# TL494_17.net
KiCad netlist of a schematic drawn in Altium Designer
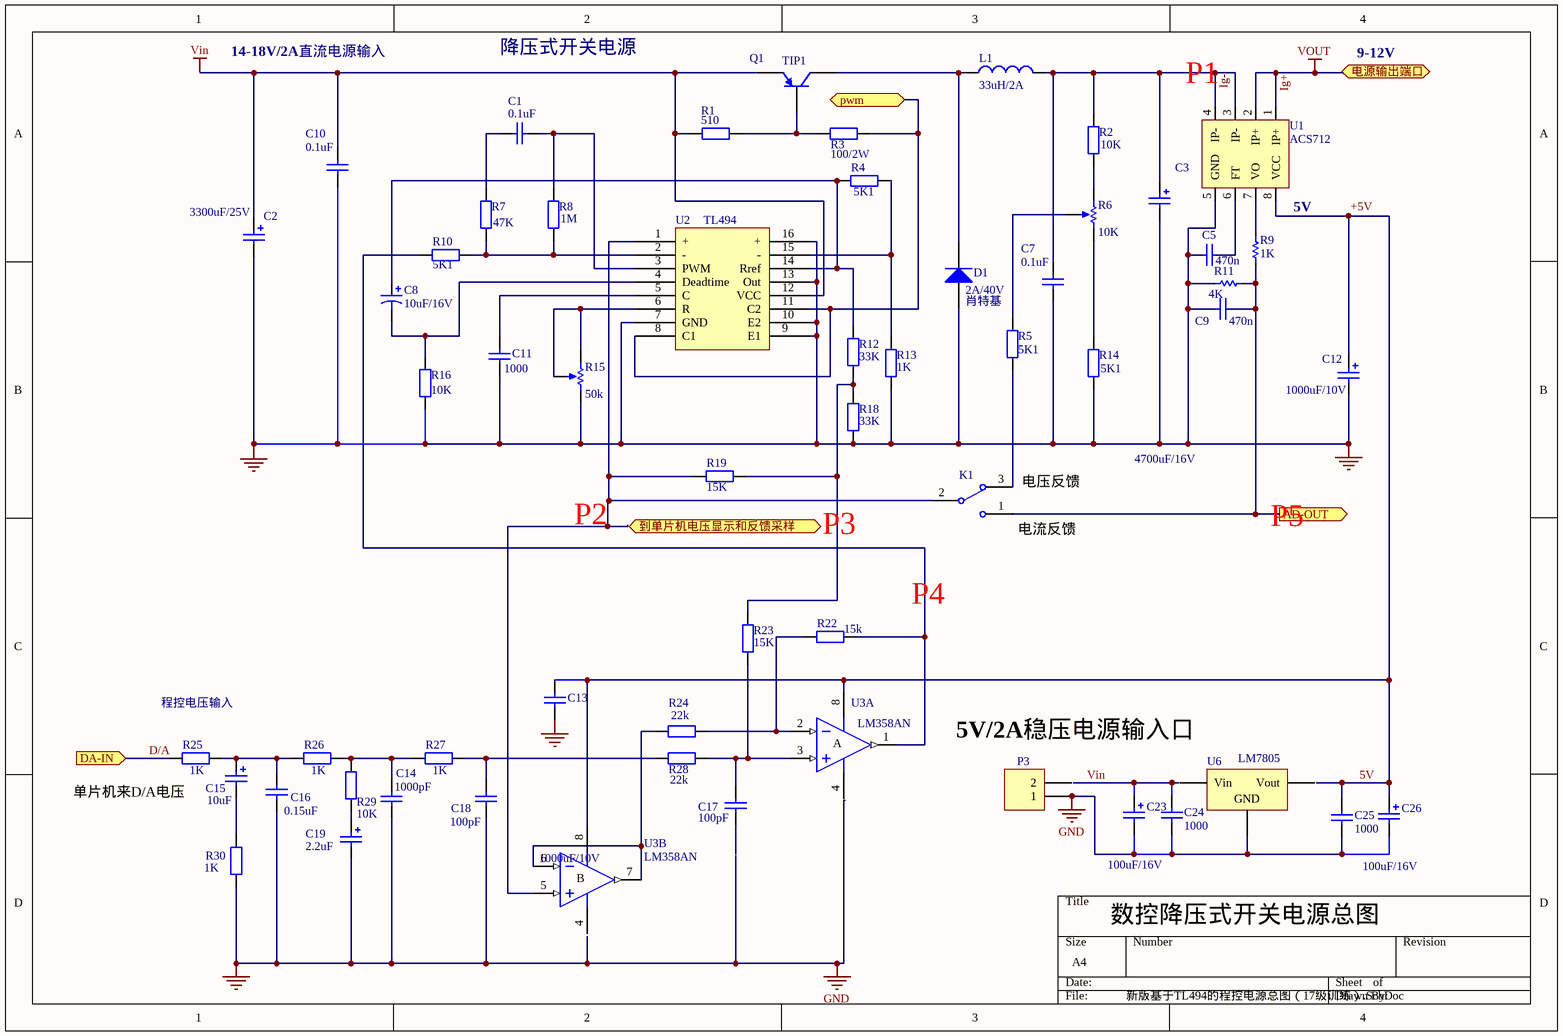
[diagram p0: 新版基于TL494的程控电源总图（17级训练）.SchDoc]

(export (version "E")
  (design (tool "Eeschema 10.0.6"))
  (components
    (comp (ref "C1")
      (value "0.1uF")
      (footprint "Cap")
      (description "Capacitor")
      (fields (field (name "Comment") "Cap") (field (name "PUBLISHER") "Altium Limited"))
      (libsource (lib "Miscellaneous Devices") (part "Cap"))
    )
    (comp (ref "C2")
      (value "3300uF/25V")
      (footprint "POLAR0.8")
      (description "Polarized Capacitor (Axial)")
      (fields (field (name "Comment") "Cap Pol2") (field (name "PUBLISHER") "Altium Limited"))
      (libsource (lib "Miscellaneous Devices") (part "Cap Pol2"))
    )
    (comp (ref "C3")
      (value "4700uF/16V")
      (footprint "POLAR0.8")
      (description "Polarized Capacitor (Axial)")
      (fields (field (name "Comment") "Cap Pol2") (field (name "PUBLISHER") "Altium Limited"))
      (libsource (lib "Miscellaneous Devices") (part "Cap Pol2"))
    )
    (comp (ref "C5")
      (value "470n")
      (footprint "1206")
      (description "ECQ-U2A334ML")
      (fields (field (name "Comment") "275VAC") (field (name "PUBLISHER") "Altium Limited"))
      (libsource (lib "Sheet1") (part "Cap"))
    )
    (comp (ref "C7")
      (value "0.1uF")
      (footprint "RAD-0.3")
      (description "Capacitor")
      (fields (field (name "Comment") "Cap") (field (name "PUBLISHER") "Altium Limited"))
      (libsource (lib "Miscellaneous Devices") (part "Cap"))
    )
    (comp (ref "C8")
      (value "10uF/16V")
      (footprint "RB7.6-15")
      (description "Polarized Capacitor (Radial)")
      (fields (field (name "Comment") "Cap Pol1") (field (name "PUBLISHER") "Altium Limited"))
      (libsource (lib "Miscellaneous Devices") (part "Cap Pol1"))
    )
    (comp (ref "C9")
      (value "470n")
      (footprint "1206")
      (description "ECQ-U2A334ML")
      (fields (field (name "Comment") "275VAC") (field (name "PUBLISHER") "Altium Limited"))
      (libsource (lib "Sheet1") (part "Cap"))
    )
    (comp (ref "C10")
      (value "0.1uF")
      (footprint "RAD-0.3")
      (description "Capacitor")
      (fields (field (name "Comment") "Cap") (field (name "PUBLISHER") "Altium Limited"))
      (libsource (lib "Miscellaneous Devices") (part "Cap"))
    )
    (comp (ref "C11")
      (value "1000")
      (footprint "Cap")
      (description "Capacitor")
      (fields (field (name "Comment") "Cap") (field (name "PUBLISHER") "Altium Limited"))
      (libsource (lib "Miscellaneous Devices") (part "Cap"))
    )
    (comp (ref "C12")
      (value "1000uF/10V")
      (footprint "POLAR0.8")
      (description "Polarized Capacitor (Axial)")
      (fields (field (name "Comment") "Cap Pol2") (field (name "PUBLISHER") "Altium Limited"))
      (libsource (lib "Miscellaneous Devices") (part "Cap Pol2"))
    )
    (comp (ref "C13")
      (value "1000uF/10V")
      (footprint "RAD-0.3")
      (description "Capacitor")
      (fields (field (name "Comment") "Cap") (field (name "PUBLISHER") "Altium Limited"))
      (libsource (lib "Miscellaneous Devices") (part "Cap"))
    )
    (comp (ref "C14")
      (value "1000pF")
      (footprint "RAD-0.3")
      (description "Capacitor")
      (fields (field (name "Comment") "Cap") (field (name "PUBLISHER") "Altium Limited"))
      (libsource (lib "Miscellaneous Devices") (part "Cap"))
    )
    (comp (ref "C15")
      (value "10uF")
      (footprint "RAD-0.3")
      (description "Polarized Capacitor (Axial)")
      (fields (field (name "Comment") "Cap Pol2") (field (name "PUBLISHER") "Altium Limited"))
      (libsource (lib "Miscellaneous Devices") (part "Cap Pol2"))
    )
    (comp (ref "C16")
      (value "0.15uF")
      (footprint "RAD-0.3")
      (description "Capacitor")
      (fields (field (name "Comment") "Cap") (field (name "PUBLISHER") "Altium Limited"))
      (libsource (lib "Miscellaneous Devices") (part "Cap"))
    )
    (comp (ref "C17")
      (value "100pF")
      (footprint "C1206")
      (description "Capacitor (Semiconductor SIM Model)")
      (fields (field (name "Comment") "Cap Semi") (field (name "PUBLISHER") "Altium Limited"))
      (libsource (lib "Miscellaneous Devices") (part "Cap Semi"))
    )
    (comp (ref "C18")
      (value "100pF")
      (footprint "RAD-0.3")
      (description "Capacitor")
      (fields (field (name "Comment") "Cap") (field (name "PUBLISHER") "Altium Limited"))
      (libsource (lib "Miscellaneous Devices") (part "Cap"))
    )
    (comp (ref "C19")
      (value "2.2uF")
      (footprint "RAD-0.3")
      (description "Polarized Capacitor (Axial)")
      (fields (field (name "Comment") "Cap Pol2") (field (name "PUBLISHER") "Altium Limited"))
      (libsource (lib "Miscellaneous Devices") (part "Cap Pol2"))
    )
    (comp (ref "C23")
      (value "100uF/16V")
      (footprint "POLAR0.8")
      (description "Polarized Capacitor (Axial)")
      (fields (field (name "Comment") "Cap Pol2") (field (name "PUBLISHER") "Altium Limited"))
      (libsource (lib "Miscellaneous Devices") (part "Cap Pol2"))
    )
    (comp (ref "C24")
      (value "1000")
      (footprint "RAD-0.3")
      (description "Capacitor")
      (fields (field (name "Comment") "Cap") (field (name "PUBLISHER") "Altium Limited"))
      (libsource (lib "Miscellaneous Devices") (part "Cap"))
    )
    (comp (ref "C25")
      (value "1000")
      (footprint "RAD-0.3")
      (description "Capacitor")
      (fields (field (name "Comment") "Cap") (field (name "PUBLISHER") "Altium Limited"))
      (libsource (lib "Miscellaneous Devices") (part "Cap"))
    )
    (comp (ref "C26")
      (value "100uF/16V")
      (footprint "POLAR0.8")
      (description "Polarized Capacitor (Axial)")
      (fields (field (name "Comment") "Cap Pol2") (field (name "PUBLISHER") "Altium Limited"))
      (libsource (lib "Miscellaneous Devices") (part "Cap Pol2"))
    )
    (comp (ref "D1")
      (value "2A/40V")
      (footprint "SMC")
      (description "Default Diode")
      (fields (field (name "PACKAGEREFERENCE") "肖特基") (field (name "PUBLISHER") "Altium Limited"))
      (libsource (lib "Miscellaneous Devices") (part "Diode"))
    )
    (comp (ref "K1")
      (value "SW-SPDT")
      (footprint "TL36WW15050")
      (description "SPDT Subminiature Toggle Switch, Right Angle Mounting, Vertical Actuation")
      (fields (field (name "PUBLISHER") "Altium Limited"))
      (libsource (lib "Miscellaneous Devices") (part "SW-SPDT"))
    )
    (comp (ref "L1")
      (value "33uH/2A")
      (footprint "INDC3216")
      (description "Inductor")
      (fields (field (name "PUBLISHER") "Altium Limited"))
      (libsource (lib "Miscellaneous Devices") (part "Inductor"))
    )
    (comp (ref "P3")
      (value "MHDR1X2")
      (footprint "MHDR1X2")
      (description "Header, 2-Pin")
      (fields (field (name "PUBLISHER") "Altium Limited"))
      (libsource (lib "Miscellaneous Connectors") (part "MHDR1X2"))
    )
    (comp (ref "R1")
      (value "510")
      (footprint "AXIAL-0.4")
      (description "Resistor")
      (fields (field (name "Comment") "Res2") (field (name "PUBLISHER") "Altium Limited"))
      (libsource (lib "Miscellaneous Devices") (part "Res2"))
    )
    (comp (ref "R2")
      (value "10K")
      (footprint "AXIAL-0.4")
      (description "Resistor")
      (fields (field (name "Comment") "Res2") (field (name "PUBLISHER") "Altium Limited"))
      (libsource (lib "") (part "Res2_1"))
    )
    (comp (ref "R3")
      (value "100/2W")
      (footprint "AXIAL-0.4")
      (description "Resistor")
      (fields (field (name "Comment") "Res2") (field (name "PUBLISHER") "Altium Limited"))
      (libsource (lib "Miscellaneous Devices") (part "Res2"))
    )
    (comp (ref "R4")
      (value "5K1")
      (footprint "AXIAL-0.4")
      (description "Resistor")
      (fields (field (name "Comment") "Res2") (field (name "PUBLISHER") "Altium Limited"))
      (libsource (lib "Miscellaneous Devices") (part "Res2"))
    )
    (comp (ref "R5")
      (value "5K1")
      (footprint "AXIAL-0.4")
      (description "Resistor")
      (fields (field (name "Comment") "Res2") (field (name "PUBLISHER") "Altium Limited"))
      (libsource (lib "") (part "Res2_1"))
    )
    (comp (ref "R6")
      (value "10K")
      (footprint "VR5")
      (description "Potentiometer")
      (fields (field (name "Comment") "RPot") (field (name "PUBLISHER") "Altium Limited"))
      (libsource (lib "Miscellaneous Devices") (part "RPot"))
    )
    (comp (ref "R7")
      (value "47K")
      (footprint "AXIAL-0.4")
      (description "Resistor")
      (fields (field (name "Comment") "Res2") (field (name "PUBLISHER") "Altium Limited"))
      (libsource (lib "") (part "Res2_1"))
    )
    (comp (ref "R8")
      (value "1M")
      (footprint "AXIAL-0.4")
      (description "Resistor")
      (fields (field (name "Comment") "Res2") (field (name "PUBLISHER") "Altium Limited"))
      (libsource (lib "") (part "Res2_1"))
    )
    (comp (ref "R9")
      (value "1K")
      (footprint "1206")
      (description "ERJ-8GEYJ2R0V")
      (fields (field (name "Comment") "1/4W") (field (name "PUBLISHER") "Altium Limited"))
      (libsource (lib "Sheet1") (part "Res1"))
    )
    (comp (ref "R10")
      (value "5K1")
      (footprint "AXIAL-0.4")
      (description "Resistor")
      (fields (field (name "Comment") "Res2") (field (name "PUBLISHER") "Altium Limited"))
      (libsource (lib "Miscellaneous Devices") (part "Res2"))
    )
    (comp (ref "R11")
      (value "4K")
      (footprint "1206")
      (description "ERJ-8GEYJ2R0V")
      (fields (field (name "Comment") "1/4W") (field (name "PUBLISHER") "Altium Limited"))
      (libsource (lib "Sheet1") (part "Res1"))
    )
    (comp (ref "R12")
      (value "33K")
      (footprint "AXIAL-0.4")
      (description "Resistor")
      (fields (field (name "Comment") "Res2") (field (name "PUBLISHER") "Altium Limited"))
      (libsource (lib "") (part "Res2_1"))
    )
    (comp (ref "R13")
      (value "1K")
      (footprint "AXIAL-0.4")
      (description "Resistor")
      (fields (field (name "Comment") "Res2") (field (name "PUBLISHER") "Altium Limited"))
      (libsource (lib "") (part "Res2_1"))
    )
    (comp (ref "R14")
      (value "5K1")
      (footprint "AXIAL-0.4")
      (description "Resistor")
      (fields (field (name "Comment") "Res2") (field (name "PUBLISHER") "Altium Limited"))
      (libsource (lib "") (part "Res2_1"))
    )
    (comp (ref "R15")
      (value "50k")
      (footprint "VR5")
      (description "Potentiometer")
      (fields (field (name "Comment") "RPot") (field (name "PUBLISHER") "Altium Limited"))
      (libsource (lib "Miscellaneous Devices") (part "RPot"))
    )
    (comp (ref "R16")
      (value "10K")
      (footprint "AXIAL-0.4")
      (description "Resistor")
      (fields (field (name "Comment") "Res2") (field (name "PUBLISHER") "Altium Limited"))
      (libsource (lib "") (part "Res2_1"))
    )
    (comp (ref "R18")
      (value "33K")
      (footprint "AXIAL-0.4")
      (description "Resistor")
      (fields (field (name "Comment") "Res2") (field (name "PUBLISHER") "Altium Limited"))
      (libsource (lib "") (part "Res2_1"))
    )
    (comp (ref "R19")
      (value "15K")
      (footprint "AXIAL-0.4")
      (description "Resistor")
      (fields (field (name "Comment") "Res2") (field (name "PUBLISHER") "Altium Limited"))
      (libsource (lib "") (part "Res2_2"))
    )
    (comp (ref "R22")
      (value "15k")
      (footprint "AXIAL-0.3")
      (description "Resistor")
      (fields (field (name "Comment") "Res2") (field (name "PUBLISHER") "Altium Limited"))
      (libsource (lib "Miscellaneous Devices") (part "Res2"))
    )
    (comp (ref "R23")
      (value "15K")
      (footprint "AXIAL-0.4")
      (description "Resistor")
      (fields (field (name "Comment") "Res2") (field (name "PUBLISHER") "Altium Limited"))
      (libsource (lib "") (part "Res2_1"))
    )
    (comp (ref "R24")
      (value "22k")
      (footprint "AXIAL-0.3")
      (description "Resistor")
      (fields (field (name "Comment") "Res2") (field (name "PUBLISHER") "Altium Limited"))
      (libsource (lib "Miscellaneous Devices") (part "Res2"))
    )
    (comp (ref "R25")
      (value "1K")
      (footprint "AXIAL-0.4")
      (description "Resistor")
      (fields (field (name "Comment") "Res2") (field (name "PUBLISHER") "Altium Limited"))
      (libsource (lib "Miscellaneous Devices") (part "Res2"))
    )
    (comp (ref "R26")
      (value "1K")
      (footprint "AXIAL-0.4")
      (description "Resistor")
      (fields (field (name "Comment") "Res2") (field (name "PUBLISHER") "Altium Limited"))
      (libsource (lib "Miscellaneous Devices") (part "Res2"))
    )
    (comp (ref "R27")
      (value "1K")
      (footprint "AXIAL-0.4")
      (description "Resistor")
      (fields (field (name "Comment") "Res2") (field (name "PUBLISHER") "Altium Limited"))
      (libsource (lib "Miscellaneous Devices") (part "Res2"))
    )
    (comp (ref "R28")
      (value "22k")
      (footprint "AXIAL-0.3")
      (description "Resistor")
      (fields (field (name "Comment") "Res2") (field (name "PUBLISHER") "Altium Limited"))
      (libsource (lib "Miscellaneous Devices") (part "Res2"))
    )
    (comp (ref "R29")
      (value "10K")
      (footprint "AXIAL-0.4")
      (description "Resistor")
      (fields (field (name "Comment") "Res2") (field (name "PUBLISHER") "Altium Limited"))
      (libsource (lib "") (part "Res2_1"))
    )
    (comp (ref "R30")
      (value "1K")
      (footprint "AXIAL-0.4")
      (description "Resistor")
      (fields (field (name "Comment") "Res2") (field (name "PUBLISHER") "Altium Limited"))
      (libsource (lib "") (part "Res2_1"))
    )
    (comp (ref "TIP1")
      (value "Q1")
      (footprint "SOT-23B_N")
      (description "PNP Bipolar Transistor")
      (fields (field (name "PUBLISHER") "Altium Limited"))
      (libsource (lib "Miscellaneous Devices") (part "PNP"))
    )
    (comp (ref "U1") (value "ACS712") (footprint "IR2111S_dip") (libsource (lib "Sheet1") (part "ACS712")))
    (comp (ref "U2") (value "TL494") (footprint "DIP16") (libsource (lib "Tl494") (part "Tl494")))
    (comp (ref "U3")
      (value "LM358AN")
      (footprint "DIP-14")
      (description "Low-Power Quad Operational Amplifier")
      (fields (field (name "PUBLISHER") "Altium Limited"))
      (libsource (lib "") (part "LM324AN_1"))
    )
    (comp (ref "U6")
      (value "LM7805")
      (footprint "D2PAK")
      (description "Voltage Regulator")
      (fields (field (name "PUBLISHER") "Altium Limited"))
      (libsource (lib "Miscellaneous Devices") (part "Volt Reg"))
    )
  )
  (nets
    (net (code "2") (name "/5V") (class "Default")
      (node (ref "C12") (pin "1") (pinfunction "1_1") (pintype "passive"))
      (node (ref "C13") (pin "2") (pinfunction "2_2") (pintype "passive"))
      (node (ref "C25") (pin "2") (pinfunction "2_2") (pintype "passive"))
      (node (ref "C26") (pin "1") (pinfunction "1_1") (pintype "passive"))
      (node (ref "U1") (pin "8") (pinfunction "VCC_8") (pintype "passive"))
      (node (ref "U3") (pin "8") (pinfunction "V+_8") (pintype "power_in"))
    )
    (net (code "3") (name "/AD-OUT") (class "Default")
      (node (ref "C9") (pin "1") (pinfunction "1_1") (pintype "passive"))
      (node (ref "K1") (pin "1") (pinfunction "1_1") (pintype "passive"))
      (node (ref "R11") (pin "2") (pinfunction "2_2") (pintype "passive"))
      (node (ref "R9") (pin "2") (pinfunction "2_2") (pintype "passive"))
    )
    (net (code "4") (name "/D{slash}A") (class "Default")
      (node (ref "R25") (pin "1") (pinfunction "1_1") (pintype "passive"))
    )
    (net (code "5") (name "/Ig-") (class "Default")
      (node (ref "C3") (pin "1") (pinfunction "1_1") (pintype "passive"))
      (node (ref "C7") (pin "2") (pinfunction "2_2") (pintype "passive"))
      (node (ref "L1") (pin "2") (pinfunction "2_2") (pintype "passive"))
      (node (ref "R2") (pin "2") (pinfunction "2_2") (pintype "passive"))
      (node (ref "U1") (pin "3") (pinfunction "IP-_3") (pintype "passive"))
      (node (ref "U1") (pin "4") (pinfunction "IP-_4") (pintype "passive"))
    )
    (net (code "6") (name "/pwm") (class "Default")
      (node (ref "R3") (pin "2") (pinfunction "2_2") (pintype "passive"))
      (node (ref "U2") (pin "11") (pinfunction "C2_11") (pintype "passive"))
      (node (ref "U2") (pin "8") (pinfunction "C1_8") (pintype "passive"))
    )
    (net (code "9") (name "GND") (class "Default")
      (node (ref "C10") (pin "1") (pinfunction "1_1") (pintype "passive"))
      (node (ref "C11") (pin "1") (pinfunction "1_1") (pintype "passive"))
      (node (ref "C12") (pin "2") (pinfunction "2_2") (pintype "passive"))
      (node (ref "C13") (pin "1") (pinfunction "1_1") (pintype "passive"))
      (node (ref "C14") (pin "1") (pinfunction "1_1") (pintype "passive"))
      (node (ref "C16") (pin "1") (pinfunction "1_1") (pintype "passive"))
      (node (ref "C18") (pin "1") (pinfunction "1_1") (pintype "passive"))
      (node (ref "C19") (pin "2") (pinfunction "2_2") (pintype "passive"))
      (node (ref "C2") (pin "2") (pinfunction "2_2") (pintype "passive"))
      (node (ref "C23") (pin "2") (pinfunction "2_2") (pintype "passive"))
      (node (ref "C24") (pin "1") (pinfunction "1_1") (pintype "passive"))
      (node (ref "C25") (pin "1") (pinfunction "1_1") (pintype "passive"))
      (node (ref "C26") (pin "2") (pinfunction "2_2") (pintype "passive"))
      (node (ref "C3") (pin "2") (pinfunction "2_2") (pintype "passive"))
      (node (ref "C5") (pin "1") (pinfunction "1_1") (pintype "passive"))
      (node (ref "C7") (pin "1") (pinfunction "1_1") (pintype "passive"))
      (node (ref "C9") (pin "2") (pinfunction "2_2") (pintype "passive"))
      (node (ref "D1") (pin "1") (pinfunction "A_1") (pintype "passive"))
      (node (ref "P3") (pin "1") (pinfunction "1_1") (pintype "passive"))
      (node (ref "R11") (pin "1") (pinfunction "1_1") (pintype "passive"))
      (node (ref "R13") (pin "1") (pinfunction "1_1") (pintype "passive"))
      (node (ref "R14") (pin "1") (pinfunction "1_1") (pintype "passive"))
      (node (ref "R15") (pin "2") (pinfunction "BOT_2") (pintype "passive"))
      (node (ref "R16") (pin "1") (pinfunction "1_1") (pintype "passive"))
      (node (ref "R18") (pin "1") (pinfunction "1_1") (pintype "passive"))
      (node (ref "R30") (pin "1") (pinfunction "1_1") (pintype "passive"))
      (node (ref "U1") (pin "5") (pinfunction "GND_5") (pintype "passive"))
      (node (ref "U2") (pin "10") (pinfunction "E2_10") (pintype "passive"))
      (node (ref "U2") (pin "13") (pinfunction "Out_13") (pintype "passive"))
      (node (ref "U2") (pin "16") (pinfunction "+_16") (pintype "passive"))
      (node (ref "U2") (pin "7") (pinfunction "GND_7") (pintype "passive"))
      (node (ref "U2") (pin "9") (pinfunction "E1_9") (pintype "passive"))
      (node (ref "U6") (pin "2") (pinfunction "GND_2") (pintype "passive"))
    )
    (net (code "10") (name "Net-(C1-Pad2)") (class "Default")
      (node (ref "C1") (pin "2") (pinfunction "2_2") (pintype "passive"))
      (node (ref "R7") (pin "2") (pinfunction "2_2") (pintype "passive"))
    )
    (net (code "11") (name "Net-(C14-Pad2)") (class "Default")
      (node (ref "C14") (pin "2") (pinfunction "2_2") (pintype "passive"))
      (node (ref "R26") (pin "2") (pinfunction "2_2") (pintype "passive"))
      (node (ref "R27") (pin "1") (pinfunction "1_1") (pintype "passive"))
      (node (ref "R29") (pin "2") (pinfunction "2_2") (pintype "passive"))
    )
    (net (code "12") (name "Net-(C15-Pad1)") (class "Default")
      (node (ref "C15") (pin "1") (pinfunction "1_1") (pintype "passive"))
      (node (ref "C16") (pin "2") (pinfunction "2_2") (pintype "passive"))
      (node (ref "R25") (pin "2") (pinfunction "2_2") (pintype "passive"))
      (node (ref "R26") (pin "1") (pinfunction "1_1") (pintype "passive"))
    )
    (net (code "13") (name "Net-(C15-Pad2)") (class "Default")
      (node (ref "C15") (pin "2") (pinfunction "2_2") (pintype "passive"))
      (node (ref "R30") (pin "2") (pinfunction "2_2") (pintype "passive"))
    )
    (net (code "14") (name "Net-(C18-Pad2)") (class "Default")
      (node (ref "C18") (pin "2") (pinfunction "2_2") (pintype "passive"))
      (node (ref "R27") (pin "2") (pinfunction "2_2") (pintype "passive"))
      (node (ref "R28") (pin "1") (pinfunction "1_1") (pintype "passive"))
    )
    (net (code "15") (name "Net-(C19-Pad1)") (class "Default")
      (node (ref "C19") (pin "1") (pinfunction "1_1") (pintype "passive"))
      (node (ref "R29") (pin "1") (pinfunction "1_1") (pintype "passive"))
    )
    (net (code "16") (name "Net-(D1-K)") (class "Default")
      (node (ref "D1") (pin "2") (pinfunction "K_2") (pintype "passive"))
      (node (ref "L1") (pin "1") (pinfunction "1_1") (pintype "passive"))
      (node (ref "TIP1") (pin "1") (pinfunction "C_1") (pintype "passive"))
    )
    (net (code "17") (name "Net-(K1-Pad3)") (class "Default")
      (node (ref "K1") (pin "3") (pinfunction "3_3") (pintype "passive"))
      (node (ref "R5") (pin "1") (pinfunction "1_1") (pintype "passive"))
    )
    (net (code "18") (name "Net-(R6-BOT)") (class "Default")
      (node (ref "R14") (pin "2") (pinfunction "2_2") (pintype "passive"))
      (node (ref "R6") (pin "2") (pinfunction "BOT_2") (pintype "passive"))
    )
    (net (code "19") (name "Net-(R6-TAP)") (class "Default")
      (node (ref "R5") (pin "2") (pinfunction "2_2") (pintype "passive"))
      (node (ref "R6") (pin "3") (pinfunction "TAP_3") (pintype "passive"))
    )
    (net (code "20") (name "Net-(R6-TOP)") (class "Default")
      (node (ref "R2") (pin "1") (pinfunction "1_1") (pintype "passive"))
      (node (ref "R6") (pin "1") (pinfunction "TOP_1") (pintype "passive"))
    )
    (net (code "21") (name "Net-(R10-Pad2)") (class "Default")
      (node (ref "R10") (pin "2") (pinfunction "2_2") (pintype "passive"))
      (node (ref "R7") (pin "1") (pinfunction "1_1") (pintype "passive"))
      (node (ref "R8") (pin "1") (pinfunction "1_1") (pintype "passive"))
      (node (ref "U2") (pin "2") (pinfunction "-_2") (pintype "passive"))
    )
    (net (code "22") (name "Net-(R12-Pad1)") (class "Default")
      (node (ref "R12") (pin "1") (pinfunction "1_1") (pintype "passive"))
      (node (ref "R18") (pin "2") (pinfunction "2_2") (pintype "passive"))
      (node (ref "R19") (pin "1") (pinfunction "1_1") (pintype "passive"))
      (node (ref "R23") (pin "2") (pinfunction "2_2") (pintype "passive"))
    )
    (net (code "23") (name "Net-(R13-Pad2)") (class "Default")
      (node (ref "R13") (pin "2") (pinfunction "2_2") (pintype "passive"))
      (node (ref "R4") (pin "2") (pinfunction "2_2") (pintype "passive"))
      (node (ref "U2") (pin "15") (pinfunction "-_15") (pintype "passive"))
    )
    (net (code "24") (name "Net-(R15-TAP)") (class "Default")
      (node (ref "R15") (pin "1") (pinfunction "TOP_1") (pintype "passive"))
      (node (ref "R15") (pin "3") (pinfunction "TAP_3") (pintype "passive"))
      (node (ref "U2") (pin "6") (pinfunction "R_6") (pintype "passive"))
    )
    (net (code "25") (name "Net-(TIP1-B)") (class "Default")
      (node (ref "R1") (pin "2") (pinfunction "2_2") (pintype "passive"))
      (node (ref "R3") (pin "1") (pinfunction "1_1") (pintype "passive"))
      (node (ref "TIP1") (pin "2") (pinfunction "B_2") (pintype "passive"))
    )
    (net (code "26") (name "Net-(TIP1-E)") (class "Default")
      (node (ref "C10") (pin "2") (pinfunction "2_2") (pintype "passive"))
      (node (ref "C2") (pin "1") (pinfunction "1_1") (pintype "passive"))
      (node (ref "R1") (pin "1") (pinfunction "1_1") (pintype "passive"))
      (node (ref "TIP1") (pin "3") (pinfunction "E_3") (pintype "passive"))
      (node (ref "U2") (pin "12") (pinfunction "VCC_12") (pintype "passive"))
    )
    (net (code "27") (name "Net-(U1-FT)") (class "Default")
      (node (ref "C5") (pin "2") (pinfunction "2_2") (pintype "passive"))
      (node (ref "U1") (pin "6") (pinfunction "FT_6") (pintype "passive"))
    )
    (net (code "28") (name "Net-(U1-VO)") (class "Default")
      (node (ref "R9") (pin "1") (pinfunction "1_1") (pintype "passive"))
      (node (ref "U1") (pin "7") (pinfunction "VO_7") (pintype "passive"))
    )
    (net (code "29") (name "Net-(U2-C)") (class "Default")
      (node (ref "C11") (pin "2") (pinfunction "2_2") (pintype "passive"))
      (node (ref "U2") (pin "5") (pinfunction "C_5") (pintype "passive"))
    )
    (net (code "30") (name "Net-(U2-Deadtime)") (class "Default")
      (node (ref "C8") (pin "2") (pinfunction "2_2") (pintype "passive"))
      (node (ref "R16") (pin "2") (pinfunction "2_2") (pintype "passive"))
      (node (ref "U2") (pin "4") (pinfunction "Deadtime_4") (pintype "passive"))
    )
    (net (code "31") (name "Net-(U2-PWM)") (class "Default")
      (node (ref "C1") (pin "1") (pinfunction "1_1") (pintype "passive"))
      (node (ref "R8") (pin "2") (pinfunction "2_2") (pintype "passive"))
      (node (ref "U2") (pin "3") (pinfunction "PWM_3") (pintype "passive"))
    )
    (net (code "32") (name "Net-(U2-Rref)") (class "Default")
      (node (ref "C8") (pin "1") (pinfunction "1_1") (pintype "passive"))
      (node (ref "R12") (pin "2") (pinfunction "2_2") (pintype "passive"))
      (node (ref "R4") (pin "1") (pinfunction "1_1") (pintype "passive"))
      (node (ref "U2") (pin "14") (pinfunction "Rref_14") (pintype "passive"))
    )
    (net (code "33") (name "Net-(U3A-IN+)") (class "Default")
      (node (ref "C17") (pin "2") (pinfunction "2_2") (pintype "passive"))
      (node (ref "R23") (pin "1") (pinfunction "1_1") (pintype "passive"))
      (node (ref "R28") (pin "2") (pinfunction "2_2") (pintype "passive"))
      (node (ref "U3") (pin "3") (pinfunction "IN+_3") (pintype "input"))
    )
    (net (code "34") (name "Net-(U3A-IN-)") (class "Default")
      (node (ref "R22") (pin "1") (pinfunction "1_1") (pintype "passive"))
      (node (ref "R24") (pin "2") (pinfunction "2_2") (pintype "passive"))
      (node (ref "U3") (pin "2") (pinfunction "IN-_2") (pintype "input"))
    )
    (net (code "35") (name "Net-(U3A-OUT)") (class "Default")
      (node (ref "R10") (pin "1") (pinfunction "1_1") (pintype "passive"))
      (node (ref "R22") (pin "2") (pinfunction "2_2") (pintype "passive"))
      (node (ref "U3") (pin "1") (pinfunction "OUT_1") (pintype "output"))
    )
    (net (code "36") (name "Net-(U3B-IN+)") (class "Default")
      (node (ref "K1") (pin "2") (pinfunction "2_2") (pintype "passive"))
      (node (ref "R19") (pin "2") (pinfunction "2_2") (pintype "passive"))
      (node (ref "U2") (pin "1") (pinfunction "+_1") (pintype "passive"))
      (node (ref "U3") (pin "5") (pinfunction "IN+_5") (pintype "input"))
    )
    (net (code "37") (name "Net-(U3B-IN-)") (class "Default")
      (node (ref "R24") (pin "1") (pinfunction "1_1") (pintype "passive"))
      (node (ref "U3") (pin "6") (pinfunction "IN-_6") (pintype "input"))
      (node (ref "U3") (pin "7") (pinfunction "OUT_7") (pintype "output"))
    )
    (net (code "38") (name "VOUT") (class "Default")
      (node (ref "U1") (pin "1") (pinfunction "IP+_1") (pintype "passive"))
      (node (ref "U1") (pin "2") (pinfunction "IP+_2") (pintype "passive"))
    )
    (net (code "39") (name "Vin") (class "Default")
      (node (ref "C23") (pin "1") (pinfunction "1_1") (pintype "passive"))
      (node (ref "C24") (pin "2") (pinfunction "2_2") (pintype "passive"))
    )
    (net (code "40") (name "unconnected-(C17-Pad1)") (class "Default")
      (node (ref "C17") (pin "1") (pinfunction "1_1") (pintype "passive"))
    )
    (net (code "41") (name "unconnected-(P3-Pad2)") (class "Default")
      (node (ref "P3") (pin "2") (pinfunction "2_2") (pintype "passive"))
    )
    (net (code "42") (name "unconnected-(U3A-V--Pad4)") (class "Default")
      (node (ref "U3") (pin "4") (pinfunction "V-_4") (pintype "power_in"))
    )
    (net (code "43") (name "unconnected-(U3B-V--Pad4)") (class "Default")
      (node (ref "U3") (pin "4") (pinfunction "V-_4") (pintype "power_in"))
    )
    (net (code "44") (name "unconnected-(U6-Vin-Pad1)") (class "Default")
      (node (ref "U6") (pin "1") (pinfunction "Vin_1") (pintype "passive"))
    )
    (net (code "45") (name "unconnected-(U6-Vout-Pad3)") (class "Default")
      (node (ref "U6") (pin "3") (pinfunction "Vout_3") (pintype "passive"))
    )
  )
)
